# Angelo_Dual_Filter_CTRL_v1_1.net
KiCad netlist of a schematic drawn in EAGLE
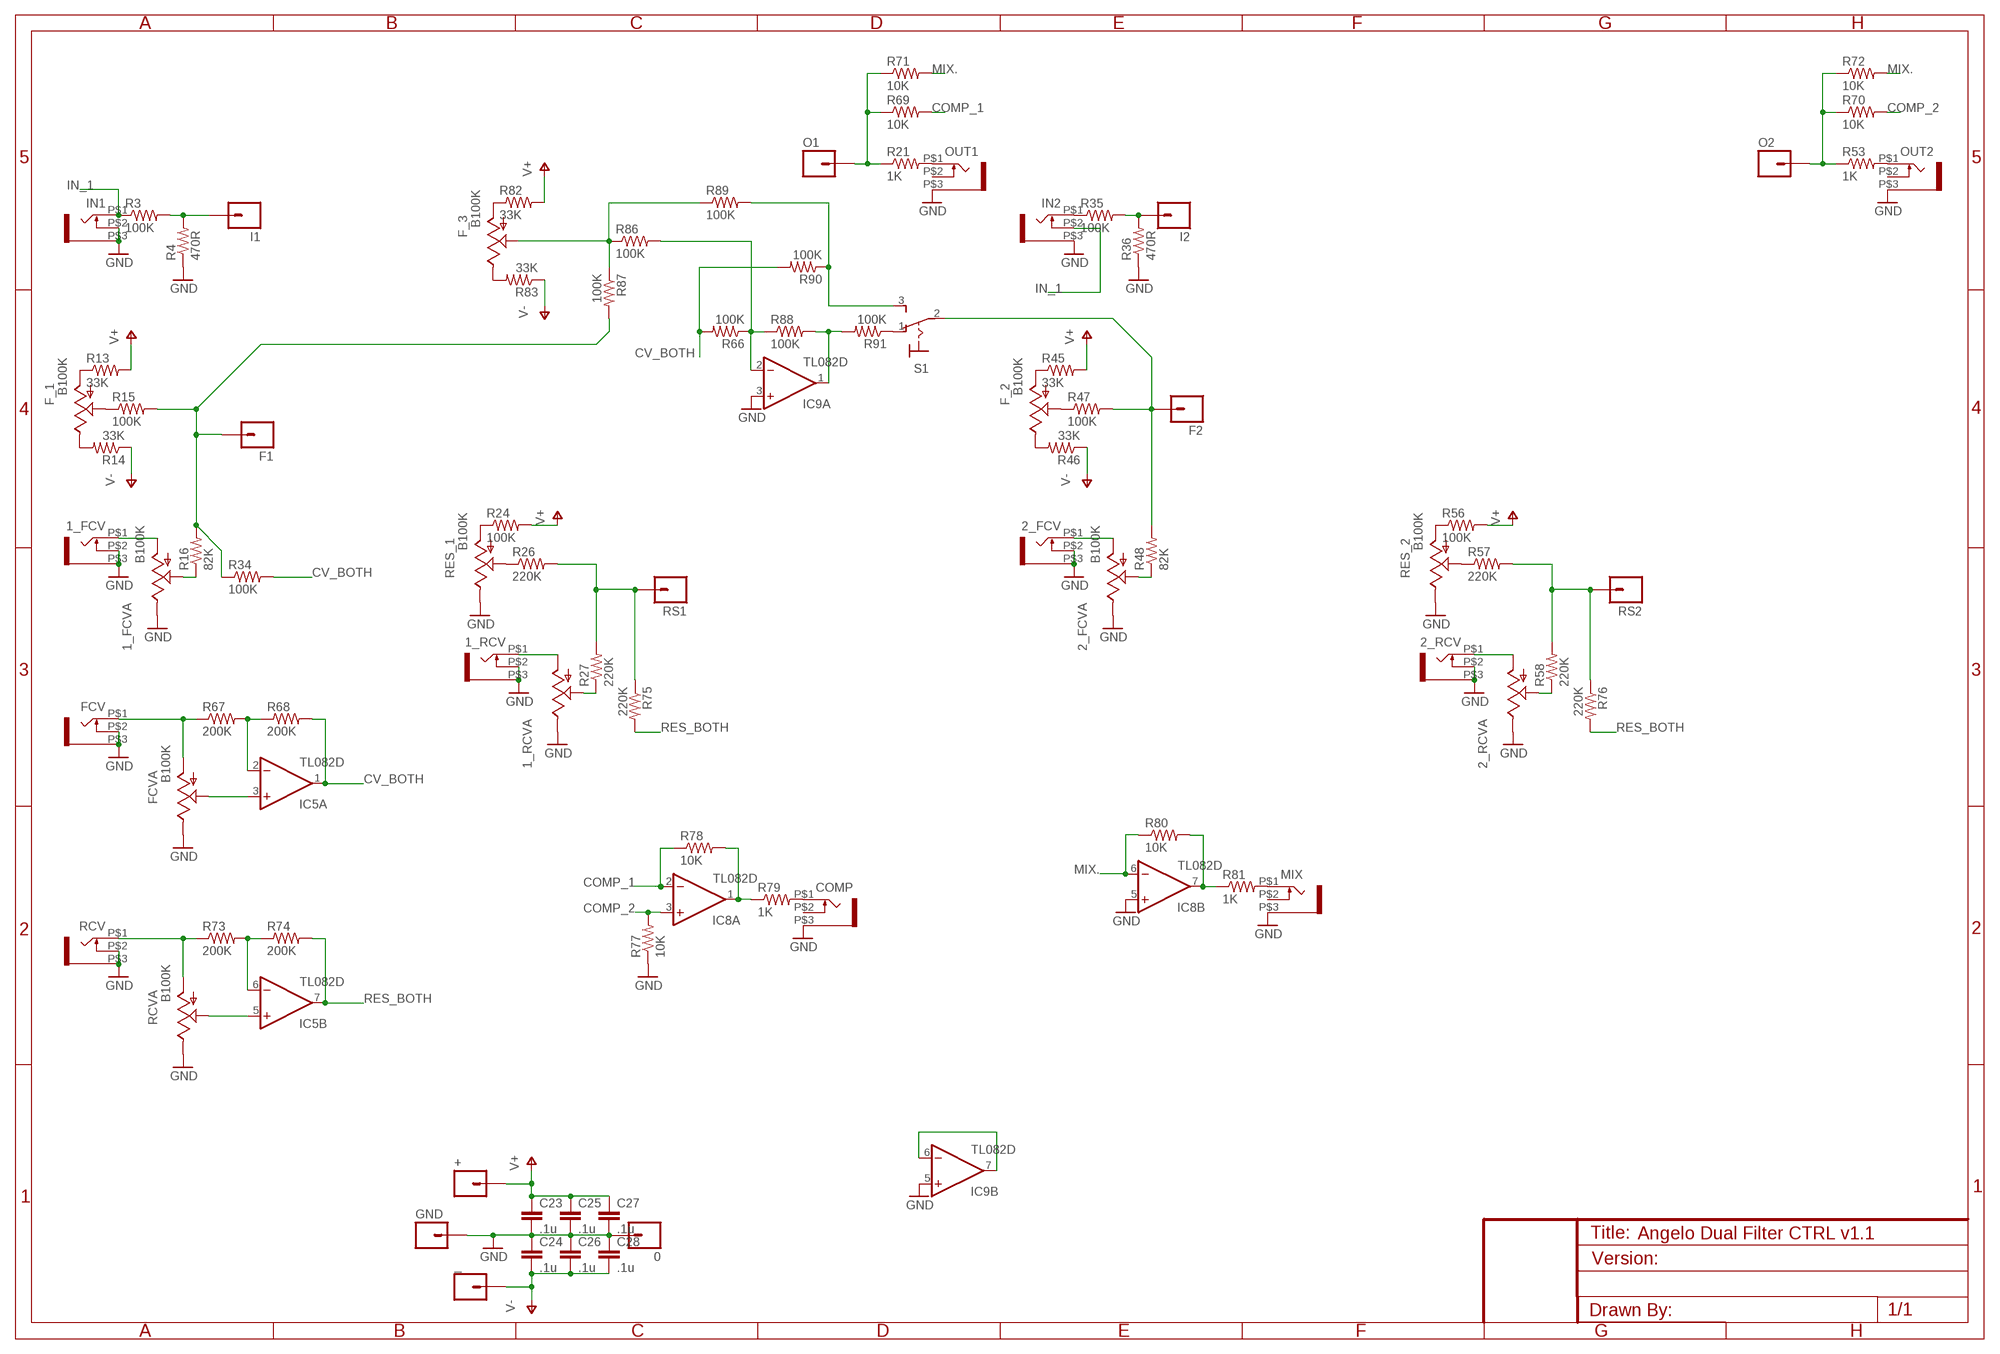
[diagram p0: schematic, sheet 1]

(export (version "E")
  (design (tool "Eeschema 10.0.6"))
  (components
    (comp (ref "+")
      (value "M01PTH")
      (footprint "eagle-import:1X01")
      (libsource (lib "eagle-import") (part "M01PTH"))
    )
    (comp (ref "0")
      (value "M01PTH")
      (footprint "eagle-import:1X01")
      (libsource (lib "eagle-import") (part "M01PTH"))
    )
    (comp (ref "1_FCV")
      (value "WQP-PJ301M-12_JACK")
      (footprint "eagle-import:WQP-PJ301M-12_JACK")
      (libsource (lib "eagle-import") (part "WQP-PJ301M-12_JACK"))
    )
    (comp (ref "1_FCVA")
      (value "B100K")
      (footprint "eagle-import:ALPS_POT")
      (libsource (lib "eagle-import") (part "POT"))
    )
    (comp (ref "1_RCV")
      (value "WQP-PJ301M-12_JACK")
      (footprint "eagle-import:WQP-PJ301M-12_JACK")
      (libsource (lib "eagle-import") (part "WQP-PJ301M-12_JACK"))
    )
    (comp (ref "1_RCVA")
      (value "POT")
      (footprint "eagle-import:ALPS_POT")
      (libsource (lib "eagle-import") (part "POT"))
    )
    (comp (ref "2_FCV")
      (value "WQP-PJ301M-12_JACK")
      (footprint "eagle-import:WQP-PJ301M-12_JACK")
      (libsource (lib "eagle-import") (part "WQP-PJ301M-12_JACK"))
    )
    (comp (ref "2_FCVA")
      (value "B100K")
      (footprint "eagle-import:ALPS_POT")
      (libsource (lib "eagle-import") (part "POT"))
    )
    (comp (ref "2_RCV")
      (value "WQP-PJ301M-12_JACK")
      (footprint "eagle-import:WQP-PJ301M-12_JACK")
      (libsource (lib "eagle-import") (part "WQP-PJ301M-12_JACK"))
    )
    (comp (ref "2_RCVA")
      (value "POT")
      (footprint "eagle-import:ALPS_POT")
      (libsource (lib "eagle-import") (part "POT"))
    )
    (comp (ref "C23")
      (value ".1u")
      (footprint "eagle-import:0805")
      (libsource (lib "eagle-import") (part "CAP0805"))
    )
    (comp (ref "C24")
      (value ".1u")
      (footprint "eagle-import:0805")
      (libsource (lib "eagle-import") (part "CAP0805"))
    )
    (comp (ref "C25")
      (value ".1u")
      (footprint "eagle-import:0805")
      (libsource (lib "eagle-import") (part "CAP0805"))
    )
    (comp (ref "C26")
      (value ".1u")
      (footprint "eagle-import:0805")
      (libsource (lib "eagle-import") (part "CAP0805"))
    )
    (comp (ref "C27")
      (value ".1u")
      (footprint "eagle-import:0805")
      (libsource (lib "eagle-import") (part "CAP0805"))
    )
    (comp (ref "C28")
      (value ".1u")
      (footprint "eagle-import:0805")
      (libsource (lib "eagle-import") (part "CAP0805"))
    )
    (comp (ref "COMP")
      (value "WQP-PJ301M-12_JACK")
      (footprint "eagle-import:WQP-PJ301M-12_JACK")
      (libsource (lib "eagle-import") (part "WQP-PJ301M-12_JACK"))
    )
    (comp (ref "F1")
      (value "M01PTH")
      (footprint "eagle-import:1X01")
      (libsource (lib "eagle-import") (part "M01PTH"))
    )
    (comp (ref "F2")
      (value "M01PTH")
      (footprint "eagle-import:1X01")
      (libsource (lib "eagle-import") (part "M01PTH"))
    )
    (comp (ref "FCV")
      (value "WQP-PJ301M-12_JACK")
      (footprint "eagle-import:WQP-PJ301M-12_JACK")
      (libsource (lib "eagle-import") (part "WQP-PJ301M-12_JACK"))
    )
    (comp (ref "FCVA")
      (value "B100K")
      (footprint "eagle-import:ALPS_POT")
      (libsource (lib "eagle-import") (part "POT"))
    )
    (comp (ref "F_1")
      (value "B100K")
      (footprint "eagle-import:ALPS_POT")
      (libsource (lib "eagle-import") (part "POT"))
    )
    (comp (ref "F_2")
      (value "B100K")
      (footprint "eagle-import:ALPS_POT")
      (libsource (lib "eagle-import") (part "POT"))
    )
    (comp (ref "F_3")
      (value "B100K")
      (footprint "eagle-import:ALPS_POT")
      (libsource (lib "eagle-import") (part "POT"))
    )
    (comp (ref "GND")
      (value "M01PTH")
      (footprint "eagle-import:1X01")
      (libsource (lib "eagle-import") (part "M01PTH"))
    )
    (comp (ref "I1")
      (value "M01PTH")
      (footprint "eagle-import:1X01")
      (libsource (lib "eagle-import") (part "M01PTH"))
    )
    (comp (ref "I2")
      (value "M01PTH")
      (footprint "eagle-import:1X01")
      (libsource (lib "eagle-import") (part "M01PTH"))
    )
    (comp (ref "IC5")
      (value "TL082D")
      (footprint "eagle-import:SO08")
      (libsource (lib "eagle-import") (part "TL082D"))
    )
    (comp (ref "IC8")
      (value "TL082D")
      (footprint "eagle-import:SO08")
      (libsource (lib "eagle-import") (part "TL082D"))
    )
    (comp (ref "IC9")
      (value "TL082D")
      (footprint "eagle-import:SO08")
      (libsource (lib "eagle-import") (part "TL082D"))
    )
    (comp (ref "IN1")
      (value "WQP-PJ301M-12_JACK")
      (footprint "eagle-import:WQP-PJ301M-12_JACK")
      (libsource (lib "eagle-import") (part "WQP-PJ301M-12_JACK"))
    )
    (comp (ref "IN2")
      (value "WQP-PJ301M-12_JACK")
      (footprint "eagle-import:WQP-PJ301M-12_JACK")
      (libsource (lib "eagle-import") (part "WQP-PJ301M-12_JACK"))
    )
    (comp (ref "MIX")
      (value "WQP-PJ301M-12_JACK")
      (footprint "eagle-import:WQP-PJ301M-12_JACK")
      (libsource (lib "eagle-import") (part "WQP-PJ301M-12_JACK"))
    )
    (comp (ref "O1")
      (value "M01PTH")
      (footprint "eagle-import:1X01")
      (libsource (lib "eagle-import") (part "M01PTH"))
    )
    (comp (ref "O2")
      (value "M01PTH")
      (footprint "eagle-import:1X01")
      (libsource (lib "eagle-import") (part "M01PTH"))
    )
    (comp (ref "OUT1")
      (value "WQP-PJ301M-12_JACK")
      (footprint "eagle-import:WQP-PJ301M-12_JACK")
      (libsource (lib "eagle-import") (part "WQP-PJ301M-12_JACK"))
    )
    (comp (ref "OUT2")
      (value "WQP-PJ301M-12_JACK")
      (footprint "eagle-import:WQP-PJ301M-12_JACK")
      (libsource (lib "eagle-import") (part "WQP-PJ301M-12_JACK"))
    )
    (comp (ref "R3")
      (value "100K")
      (footprint "eagle-import:0805")
      (libsource (lib "eagle-import") (part "RESISTOR0805-RES"))
    )
    (comp (ref "R4")
      (value "470R")
      (footprint "eagle-import:0805")
      (libsource (lib "eagle-import") (part "RESISTOR0805-RES"))
    )
    (comp (ref "R13")
      (value "33K")
      (footprint "eagle-import:0805")
      (libsource (lib "eagle-import") (part "RESISTOR0805-RES"))
    )
    (comp (ref "R14")
      (value "33K")
      (footprint "eagle-import:0805")
      (libsource (lib "eagle-import") (part "RESISTOR0805-RES"))
    )
    (comp (ref "R15")
      (value "100K")
      (footprint "eagle-import:0805")
      (libsource (lib "eagle-import") (part "RESISTOR0805-RES"))
    )
    (comp (ref "R16")
      (value "82K")
      (footprint "eagle-import:0805")
      (libsource (lib "eagle-import") (part "RESISTOR0805-RES"))
    )
    (comp (ref "R21")
      (value "1K")
      (footprint "eagle-import:0805")
      (libsource (lib "eagle-import") (part "RESISTOR0805-RES"))
    )
    (comp (ref "R24")
      (value "100K")
      (footprint "eagle-import:0805")
      (libsource (lib "eagle-import") (part "RESISTOR0805-RES"))
    )
    (comp (ref "R26")
      (value "220K")
      (footprint "eagle-import:0805")
      (libsource (lib "eagle-import") (part "RESISTOR0805-RES"))
    )
    (comp (ref "R27")
      (value "220K")
      (footprint "eagle-import:0805")
      (libsource (lib "eagle-import") (part "RESISTOR0805-RES"))
    )
    (comp (ref "R34")
      (value "100K")
      (footprint "eagle-import:0805")
      (libsource (lib "eagle-import") (part "RESISTOR0805-RES"))
    )
    (comp (ref "R35")
      (value "100K")
      (footprint "eagle-import:0805")
      (libsource (lib "eagle-import") (part "RESISTOR0805-RES"))
    )
    (comp (ref "R36")
      (value "470R")
      (footprint "eagle-import:0805")
      (libsource (lib "eagle-import") (part "RESISTOR0805-RES"))
    )
    (comp (ref "R45")
      (value "33K")
      (footprint "eagle-import:0805")
      (libsource (lib "eagle-import") (part "RESISTOR0805-RES"))
    )
    (comp (ref "R46")
      (value "33K")
      (footprint "eagle-import:0805")
      (libsource (lib "eagle-import") (part "RESISTOR0805-RES"))
    )
    (comp (ref "R47")
      (value "100K")
      (footprint "eagle-import:0805")
      (libsource (lib "eagle-import") (part "RESISTOR0805-RES"))
    )
    (comp (ref "R48")
      (value "82K")
      (footprint "eagle-import:0805")
      (libsource (lib "eagle-import") (part "RESISTOR0805-RES"))
    )
    (comp (ref "R53")
      (value "1K")
      (footprint "eagle-import:0805")
      (libsource (lib "eagle-import") (part "RESISTOR0805-RES"))
    )
    (comp (ref "R56")
      (value "100K")
      (footprint "eagle-import:0805")
      (libsource (lib "eagle-import") (part "RESISTOR0805-RES"))
    )
    (comp (ref "R57")
      (value "220K")
      (footprint "eagle-import:0805")
      (libsource (lib "eagle-import") (part "RESISTOR0805-RES"))
    )
    (comp (ref "R58")
      (value "220K")
      (footprint "eagle-import:0805")
      (libsource (lib "eagle-import") (part "RESISTOR0805-RES"))
    )
    (comp (ref "R66")
      (value "100K")
      (footprint "eagle-import:0805")
      (libsource (lib "eagle-import") (part "RESISTOR0805-RES"))
    )
    (comp (ref "R67")
      (value "200K")
      (footprint "eagle-import:0805")
      (libsource (lib "eagle-import") (part "RESISTOR0805-RES"))
    )
    (comp (ref "R68")
      (value "200K")
      (footprint "eagle-import:0805")
      (libsource (lib "eagle-import") (part "RESISTOR0805-RES"))
    )
    (comp (ref "R69")
      (value "10K")
      (footprint "eagle-import:0805")
      (libsource (lib "eagle-import") (part "RESISTOR0805-RES"))
    )
    (comp (ref "R70")
      (value "10K")
      (footprint "eagle-import:0805")
      (libsource (lib "eagle-import") (part "RESISTOR0805-RES"))
    )
    (comp (ref "R71")
      (value "10K")
      (footprint "eagle-import:0805")
      (libsource (lib "eagle-import") (part "RESISTOR0805-RES"))
    )
    (comp (ref "R72")
      (value "10K")
      (footprint "eagle-import:0805")
      (libsource (lib "eagle-import") (part "RESISTOR0805-RES"))
    )
    (comp (ref "R73")
      (value "200K")
      (footprint "eagle-import:0805")
      (libsource (lib "eagle-import") (part "RESISTOR0805-RES"))
    )
    (comp (ref "R74")
      (value "200K")
      (footprint "eagle-import:0805")
      (libsource (lib "eagle-import") (part "RESISTOR0805-RES"))
    )
    (comp (ref "R75")
      (value "220K")
      (footprint "eagle-import:0805")
      (libsource (lib "eagle-import") (part "RESISTOR0805-RES"))
    )
    (comp (ref "R76")
      (value "220K")
      (footprint "eagle-import:0805")
      (libsource (lib "eagle-import") (part "RESISTOR0805-RES"))
    )
    (comp (ref "R77")
      (value "10K")
      (footprint "eagle-import:0805")
      (libsource (lib "eagle-import") (part "RESISTOR0805-RES"))
    )
    (comp (ref "R78")
      (value "10K")
      (footprint "eagle-import:0805")
      (libsource (lib "eagle-import") (part "RESISTOR0805-RES"))
    )
    (comp (ref "R79")
      (value "1K")
      (footprint "eagle-import:0805")
      (libsource (lib "eagle-import") (part "RESISTOR0805-RES"))
    )
    (comp (ref "R80")
      (value "10K")
      (footprint "eagle-import:0805")
      (libsource (lib "eagle-import") (part "RESISTOR0805-RES"))
    )
    (comp (ref "R81")
      (value "1K")
      (footprint "eagle-import:0805")
      (libsource (lib "eagle-import") (part "RESISTOR0805-RES"))
    )
    (comp (ref "R82")
      (value "33K")
      (footprint "eagle-import:0805")
      (libsource (lib "eagle-import") (part "RESISTOR0805-RES"))
    )
    (comp (ref "R83")
      (value "33K")
      (footprint "eagle-import:0805")
      (libsource (lib "eagle-import") (part "RESISTOR0805-RES"))
    )
    (comp (ref "R86")
      (value "100K")
      (footprint "eagle-import:0805")
      (libsource (lib "eagle-import") (part "RESISTOR0805-RES"))
    )
    (comp (ref "R87")
      (value "100K")
      (footprint "eagle-import:0805")
      (libsource (lib "eagle-import") (part "RESISTOR0805-RES"))
    )
    (comp (ref "R88")
      (value "100K")
      (footprint "eagle-import:0805")
      (libsource (lib "eagle-import") (part "RESISTOR0805-RES"))
    )
    (comp (ref "R89")
      (value "100K")
      (footprint "eagle-import:0805")
      (libsource (lib "eagle-import") (part "RESISTOR0805-RES"))
    )
    (comp (ref "R90")
      (value "100K")
      (footprint "eagle-import:0805")
      (libsource (lib "eagle-import") (part "RESISTOR0805-RES"))
    )
    (comp (ref "R91")
      (value "100K")
      (footprint "eagle-import:0805")
      (libsource (lib "eagle-import") (part "RESISTOR0805-RES"))
    )
    (comp (ref "RCV")
      (value "WQP-PJ301M-12_JACK")
      (footprint "eagle-import:WQP-PJ301M-12_JACK")
      (libsource (lib "eagle-import") (part "WQP-PJ301M-12_JACK"))
    )
    (comp (ref "RCVA")
      (value "B100K")
      (footprint "eagle-import:ALPS_POT")
      (libsource (lib "eagle-import") (part "POT"))
    )
    (comp (ref "RES_1")
      (value "B100K")
      (footprint "eagle-import:ALPS_POT")
      (libsource (lib "eagle-import") (part "POT"))
    )
    (comp (ref "RES_2")
      (value "B100K")
      (footprint "eagle-import:ALPS_POT")
      (libsource (lib "eagle-import") (part "POT"))
    )
    (comp (ref "RS1")
      (value "M01PTH")
      (footprint "eagle-import:1X01")
      (libsource (lib "eagle-import") (part "M01PTH"))
    )
    (comp (ref "RS2")
      (value "M01PTH")
      (footprint "eagle-import:1X01")
      (libsource (lib "eagle-import") (part "M01PTH"))
    )
    (comp (ref "S1")
      (value "M9040P")
      (footprint "eagle-import:M9040P")
      (libsource (lib "eagle-import") (part "M9040P"))
    )
    (comp (ref "_")
      (value "M01PTH")
      (footprint "eagle-import:1X01")
      (libsource (lib "eagle-import") (part "M01PTH"))
    )
  )
  (nets
    (net (code "1") (name "/COMP_1") (class "Default")
      (node (ref "IC8") (pin "2") (pinfunction "-IN_2") (pintype "input"))
      (node (ref "R69") (pin "2") (pinfunction "2_2") (pintype "passive"))
      (node (ref "R78") (pin "1") (pinfunction "1_1") (pintype "passive"))
    )
    (net (code "2") (name "/COMP_2") (class "Default")
      (node (ref "IC8") (pin "3") (pinfunction "+IN_3") (pintype "input"))
      (node (ref "R70") (pin "2") (pinfunction "2_2") (pintype "passive"))
      (node (ref "R77") (pin "2") (pinfunction "2_2") (pintype "passive"))
    )
    (net (code "3") (name "/CV_BOTH") (class "Default")
      (node (ref "IC5") (pin "1") (pinfunction "OUT_1") (pintype "output"))
      (node (ref "R34") (pin "2") (pinfunction "2_2") (pintype "passive"))
      (node (ref "R66") (pin "2") (pinfunction "2_2") (pintype "passive"))
      (node (ref "R68") (pin "2") (pinfunction "2_2") (pintype "passive"))
      (node (ref "R90") (pin "2") (pinfunction "2_2") (pintype "passive"))
    )
    (net (code "4") (name "/IN_1") (class "Default")
      (node (ref "IN1") (pin "P$1") (pinfunction "2_P$1") (pintype "passive"))
      (node (ref "IN2") (pin "P$2") (pinfunction "3_P$2") (pintype "passive"))
      (node (ref "R3") (pin "1") (pinfunction "1_1") (pintype "passive"))
    )
    (net (code "5") (name "/MIX.") (class "Default")
      (node (ref "IC8") (pin "6") (pinfunction "-IN_6") (pintype "input"))
      (node (ref "R71") (pin "2") (pinfunction "2_2") (pintype "passive"))
      (node (ref "R72") (pin "2") (pinfunction "2_2") (pintype "passive"))
      (node (ref "R80") (pin "1") (pinfunction "1_1") (pintype "passive"))
    )
    (net (code "6") (name "/RES_BOTH") (class "Default")
      (node (ref "IC5") (pin "7") (pinfunction "OUT_7") (pintype "output"))
      (node (ref "R74") (pin "2") (pinfunction "2_2") (pintype "passive"))
      (node (ref "R75") (pin "2") (pinfunction "2_2") (pintype "passive"))
      (node (ref "R76") (pin "2") (pinfunction "2_2") (pintype "passive"))
    )
    (net (code "7") (name "GND") (class "Default")
      (node (ref "0") (pin "1") (pinfunction "1_1") (pintype "passive"))
      (node (ref "1_FCV") (pin "P$2") (pinfunction "3_P$2") (pintype "passive"))
      (node (ref "1_FCV") (pin "P$3") (pinfunction "1_P$3") (pintype "passive"))
      (node (ref "1_FCVA") (pin "P$1") (pinfunction "E_P$1") (pintype "passive"))
      (node (ref "1_RCV") (pin "P$2") (pinfunction "3_P$2") (pintype "passive"))
      (node (ref "1_RCV") (pin "P$3") (pinfunction "1_P$3") (pintype "passive"))
      (node (ref "1_RCVA") (pin "P$1") (pinfunction "E_P$1") (pintype "passive"))
      (node (ref "2_FCV") (pin "P$2") (pinfunction "3_P$2") (pintype "passive"))
      (node (ref "2_FCV") (pin "P$3") (pinfunction "1_P$3") (pintype "passive"))
      (node (ref "2_FCVA") (pin "P$1") (pinfunction "E_P$1") (pintype "passive"))
      (node (ref "2_RCV") (pin "P$2") (pinfunction "3_P$2") (pintype "passive"))
      (node (ref "2_RCV") (pin "P$3") (pinfunction "1_P$3") (pintype "passive"))
      (node (ref "2_RCVA") (pin "P$1") (pinfunction "E_P$1") (pintype "passive"))
      (node (ref "C23") (pin "2") (pinfunction "2_2") (pintype "passive"))
      (node (ref "C24") (pin "1") (pinfunction "1_1") (pintype "passive"))
      (node (ref "C25") (pin "2") (pinfunction "2_2") (pintype "passive"))
      (node (ref "C26") (pin "1") (pinfunction "1_1") (pintype "passive"))
      (node (ref "C27") (pin "2") (pinfunction "2_2") (pintype "passive"))
      (node (ref "C28") (pin "1") (pinfunction "1_1") (pintype "passive"))
      (node (ref "COMP") (pin "P$3") (pinfunction "1_P$3") (pintype "passive"))
      (node (ref "FCV") (pin "P$2") (pinfunction "3_P$2") (pintype "passive"))
      (node (ref "FCV") (pin "P$3") (pinfunction "1_P$3") (pintype "passive"))
      (node (ref "FCVA") (pin "P$1") (pinfunction "E_P$1") (pintype "passive"))
      (node (ref "GND") (pin "1") (pinfunction "1_1") (pintype "passive"))
      (node (ref "IC8") (pin "5") (pinfunction "+IN_5") (pintype "input"))
      (node (ref "IC9") (pin "3") (pinfunction "+IN_3") (pintype "input"))
      (node (ref "IC9") (pin "5") (pinfunction "+IN_5") (pintype "input"))
      (node (ref "IN1") (pin "P$2") (pinfunction "3_P$2") (pintype "passive"))
      (node (ref "IN1") (pin "P$3") (pinfunction "1_P$3") (pintype "passive"))
      (node (ref "IN2") (pin "P$3") (pinfunction "1_P$3") (pintype "passive"))
      (node (ref "MIX") (pin "P$3") (pinfunction "1_P$3") (pintype "passive"))
      (node (ref "OUT1") (pin "P$3") (pinfunction "1_P$3") (pintype "passive"))
      (node (ref "OUT2") (pin "P$3") (pinfunction "1_P$3") (pintype "passive"))
      (node (ref "R36") (pin "1") (pinfunction "1_1") (pintype "passive"))
      (node (ref "R4") (pin "1") (pinfunction "1_1") (pintype "passive"))
      (node (ref "R77") (pin "1") (pinfunction "1_1") (pintype "passive"))
      (node (ref "RCV") (pin "P$2") (pinfunction "3_P$2") (pintype "passive"))
      (node (ref "RCV") (pin "P$3") (pinfunction "1_P$3") (pintype "passive"))
      (node (ref "RCVA") (pin "P$1") (pinfunction "E_P$1") (pintype "passive"))
      (node (ref "RES_1") (pin "P$1") (pinfunction "E_P$1") (pintype "passive"))
      (node (ref "RES_2") (pin "P$1") (pinfunction "E_P$1") (pintype "passive"))
    )
    (net (code "8") (name "Net-(1_FCV-2)") (class "Default")
      (node (ref "1_FCV") (pin "P$1") (pinfunction "2_P$1") (pintype "passive"))
      (node (ref "1_FCVA") (pin "P$3") (pinfunction "A_P$3") (pintype "passive"))
    )
    (net (code "9") (name "Net-(1_FCVA-S)") (class "Default")
      (node (ref "1_FCVA") (pin "P$2") (pinfunction "S_P$2") (pintype "passive"))
      (node (ref "R16") (pin "1") (pinfunction "1_1") (pintype "passive"))
    )
    (net (code "10") (name "Net-(1_RCV-2)") (class "Default")
      (node (ref "1_RCV") (pin "P$1") (pinfunction "2_P$1") (pintype "passive"))
      (node (ref "1_RCVA") (pin "P$3") (pinfunction "A_P$3") (pintype "passive"))
    )
    (net (code "11") (name "Net-(1_RCVA-S)") (class "Default")
      (node (ref "1_RCVA") (pin "P$2") (pinfunction "S_P$2") (pintype "passive"))
      (node (ref "R27") (pin "1") (pinfunction "1_1") (pintype "passive"))
    )
    (net (code "12") (name "Net-(2_FCV-2)") (class "Default")
      (node (ref "2_FCV") (pin "P$1") (pinfunction "2_P$1") (pintype "passive"))
      (node (ref "2_FCVA") (pin "P$3") (pinfunction "A_P$3") (pintype "passive"))
    )
    (net (code "13") (name "Net-(2_FCVA-S)") (class "Default")
      (node (ref "2_FCVA") (pin "P$2") (pinfunction "S_P$2") (pintype "passive"))
      (node (ref "R48") (pin "1") (pinfunction "1_1") (pintype "passive"))
    )
    (net (code "14") (name "Net-(2_RCV-2)") (class "Default")
      (node (ref "2_RCV") (pin "P$1") (pinfunction "2_P$1") (pintype "passive"))
      (node (ref "2_RCVA") (pin "P$3") (pinfunction "A_P$3") (pintype "passive"))
    )
    (net (code "15") (name "Net-(2_RCVA-S)") (class "Default")
      (node (ref "2_RCVA") (pin "P$2") (pinfunction "S_P$2") (pintype "passive"))
      (node (ref "R58") (pin "1") (pinfunction "1_1") (pintype "passive"))
    )
    (net (code "16") (name "Net-(COMP-2)") (class "Default")
      (node (ref "COMP") (pin "P$1") (pinfunction "2_P$1") (pintype "passive"))
      (node (ref "R79") (pin "2") (pinfunction "2_2") (pintype "passive"))
    )
    (net (code "17") (name "Net-(F1-Pad1)") (class "Default")
      (node (ref "F1") (pin "1") (pinfunction "1_1") (pintype "passive"))
      (node (ref "R15") (pin "2") (pinfunction "2_2") (pintype "passive"))
      (node (ref "R16") (pin "2") (pinfunction "2_2") (pintype "passive"))
      (node (ref "R34") (pin "1") (pinfunction "1_1") (pintype "passive"))
      (node (ref "R87") (pin "2") (pinfunction "2_2") (pintype "passive"))
    )
    (net (code "18") (name "Net-(FCV-2)") (class "Default")
      (node (ref "FCV") (pin "P$1") (pinfunction "2_P$1") (pintype "passive"))
      (node (ref "FCVA") (pin "P$3") (pinfunction "A_P$3") (pintype "passive"))
      (node (ref "R67") (pin "1") (pinfunction "1_1") (pintype "passive"))
    )
    (net (code "19") (name "Net-(FCVA-S)") (class "Default")
      (node (ref "FCVA") (pin "P$2") (pinfunction "S_P$2") (pintype "passive"))
      (node (ref "IC5") (pin "3") (pinfunction "+IN_3") (pintype "input"))
    )
    (net (code "20") (name "Net-(F_1-A)") (class "Default")
      (node (ref "F_1") (pin "P$3") (pinfunction "A_P$3") (pintype "passive"))
      (node (ref "R13") (pin "1") (pinfunction "1_1") (pintype "passive"))
    )
    (net (code "21") (name "Net-(F_1-E)") (class "Default")
      (node (ref "F_1") (pin "P$1") (pinfunction "E_P$1") (pintype "passive"))
      (node (ref "R14") (pin "2") (pinfunction "2_2") (pintype "passive"))
    )
    (net (code "22") (name "Net-(F_1-S)") (class "Default")
      (node (ref "F_1") (pin "P$2") (pinfunction "S_P$2") (pintype "passive"))
      (node (ref "R15") (pin "1") (pinfunction "1_1") (pintype "passive"))
    )
    (net (code "23") (name "Net-(F_2-A)") (class "Default")
      (node (ref "F_2") (pin "P$3") (pinfunction "A_P$3") (pintype "passive"))
      (node (ref "R45") (pin "1") (pinfunction "1_1") (pintype "passive"))
    )
    (net (code "24") (name "Net-(F_2-E)") (class "Default")
      (node (ref "F_2") (pin "P$1") (pinfunction "E_P$1") (pintype "passive"))
      (node (ref "R46") (pin "2") (pinfunction "2_2") (pintype "passive"))
    )
    (net (code "25") (name "Net-(F_2-S)") (class "Default")
      (node (ref "F_2") (pin "P$2") (pinfunction "S_P$2") (pintype "passive"))
      (node (ref "R47") (pin "1") (pinfunction "1_1") (pintype "passive"))
    )
    (net (code "26") (name "Net-(F_3-A)") (class "Default")
      (node (ref "F_3") (pin "P$3") (pinfunction "A_P$3") (pintype "passive"))
      (node (ref "R82") (pin "1") (pinfunction "1_1") (pintype "passive"))
    )
    (net (code "27") (name "Net-(F_3-E)") (class "Default")
      (node (ref "F_3") (pin "P$1") (pinfunction "E_P$1") (pintype "passive"))
      (node (ref "R83") (pin "2") (pinfunction "2_2") (pintype "passive"))
    )
    (net (code "28") (name "Net-(F_3-S)") (class "Default")
      (node (ref "F_3") (pin "P$2") (pinfunction "S_P$2") (pintype "passive"))
      (node (ref "R86") (pin "1") (pinfunction "1_1") (pintype "passive"))
      (node (ref "R87") (pin "1") (pinfunction "1_1") (pintype "passive"))
      (node (ref "R89") (pin "1") (pinfunction "1_1") (pintype "passive"))
    )
    (net (code "29") (name "Net-(I1-Pad1)") (class "Default")
      (node (ref "I1") (pin "1") (pinfunction "1_1") (pintype "passive"))
      (node (ref "R3") (pin "2") (pinfunction "2_2") (pintype "passive"))
      (node (ref "R4") (pin "2") (pinfunction "2_2") (pintype "passive"))
    )
    (net (code "30") (name "Net-(I2-Pad1)") (class "Default")
      (node (ref "I2") (pin "1") (pinfunction "1_1") (pintype "passive"))
      (node (ref "R35") (pin "2") (pinfunction "2_2") (pintype "passive"))
      (node (ref "R36") (pin "2") (pinfunction "2_2") (pintype "passive"))
    )
    (net (code "31") (name "Net-(IC5A--IN)") (class "Default")
      (node (ref "IC5") (pin "2") (pinfunction "-IN_2") (pintype "input"))
      (node (ref "R67") (pin "2") (pinfunction "2_2") (pintype "passive"))
      (node (ref "R68") (pin "1") (pinfunction "1_1") (pintype "passive"))
    )
    (net (code "32") (name "Net-(IC5B-+IN)") (class "Default")
      (node (ref "IC5") (pin "5") (pinfunction "+IN_5") (pintype "input"))
      (node (ref "RCVA") (pin "P$2") (pinfunction "S_P$2") (pintype "passive"))
    )
    (net (code "33") (name "Net-(IC5B--IN)") (class "Default")
      (node (ref "IC5") (pin "6") (pinfunction "-IN_6") (pintype "input"))
      (node (ref "R73") (pin "2") (pinfunction "2_2") (pintype "passive"))
      (node (ref "R74") (pin "1") (pinfunction "1_1") (pintype "passive"))
    )
    (net (code "34") (name "Net-(IC8A-OUT)") (class "Default")
      (node (ref "IC8") (pin "1") (pinfunction "OUT_1") (pintype "output"))
      (node (ref "R78") (pin "2") (pinfunction "2_2") (pintype "passive"))
      (node (ref "R79") (pin "1") (pinfunction "1_1") (pintype "passive"))
    )
    (net (code "35") (name "Net-(IC8B-OUT)") (class "Default")
      (node (ref "IC8") (pin "7") (pinfunction "OUT_7") (pintype "output"))
      (node (ref "R80") (pin "2") (pinfunction "2_2") (pintype "passive"))
      (node (ref "R81") (pin "1") (pinfunction "1_1") (pintype "passive"))
    )
    (net (code "36") (name "Net-(IC9A--IN)") (class "Default")
      (node (ref "IC9") (pin "2") (pinfunction "-IN_2") (pintype "input"))
      (node (ref "R66") (pin "1") (pinfunction "1_1") (pintype "passive"))
      (node (ref "R86") (pin "2") (pinfunction "2_2") (pintype "passive"))
      (node (ref "R88") (pin "1") (pinfunction "1_1") (pintype "passive"))
    )
    (net (code "37") (name "Net-(IC9A-OUT)") (class "Default")
      (node (ref "IC9") (pin "1") (pinfunction "OUT_1") (pintype "output"))
      (node (ref "R88") (pin "2") (pinfunction "2_2") (pintype "passive"))
      (node (ref "R91") (pin "2") (pinfunction "2_2") (pintype "passive"))
    )
    (net (code "38") (name "Net-(IC9B--IN)") (class "Default")
      (node (ref "IC9") (pin "6") (pinfunction "-IN_6") (pintype "input"))
      (node (ref "IC9") (pin "7") (pinfunction "OUT_7") (pintype "output"))
    )
    (net (code "39") (name "Net-(IN2-2)") (class "Default")
      (node (ref "IN2") (pin "P$1") (pinfunction "2_P$1") (pintype "passive"))
      (node (ref "R35") (pin "1") (pinfunction "1_1") (pintype "passive"))
    )
    (net (code "40") (name "Net-(MIX-2)") (class "Default")
      (node (ref "MIX") (pin "P$1") (pinfunction "2_P$1") (pintype "passive"))
      (node (ref "R81") (pin "2") (pinfunction "2_2") (pintype "passive"))
    )
    (net (code "41") (name "Net-(O1-Pad1)") (class "Default")
      (node (ref "O1") (pin "1") (pinfunction "1_1") (pintype "passive"))
      (node (ref "R21") (pin "1") (pinfunction "1_1") (pintype "passive"))
      (node (ref "R69") (pin "1") (pinfunction "1_1") (pintype "passive"))
      (node (ref "R71") (pin "1") (pinfunction "1_1") (pintype "passive"))
    )
    (net (code "42") (name "Net-(O2-Pad1)") (class "Default")
      (node (ref "O2") (pin "1") (pinfunction "1_1") (pintype "passive"))
      (node (ref "R53") (pin "1") (pinfunction "1_1") (pintype "passive"))
      (node (ref "R70") (pin "1") (pinfunction "1_1") (pintype "passive"))
      (node (ref "R72") (pin "1") (pinfunction "1_1") (pintype "passive"))
    )
    (net (code "43") (name "Net-(OUT1-2)") (class "Default")
      (node (ref "OUT1") (pin "P$1") (pinfunction "2_P$1") (pintype "passive"))
      (node (ref "R21") (pin "2") (pinfunction "2_2") (pintype "passive"))
    )
    (net (code "44") (name "Net-(OUT2-2)") (class "Default")
      (node (ref "OUT2") (pin "P$1") (pinfunction "2_P$1") (pintype "passive"))
      (node (ref "R53") (pin "2") (pinfunction "2_2") (pintype "passive"))
    )
    (net (code "45") (name "Net-(R26-Pad2)") (class "Default")
      (node (ref "R26") (pin "2") (pinfunction "2_2") (pintype "passive"))
      (node (ref "R27") (pin "2") (pinfunction "2_2") (pintype "passive"))
      (node (ref "R75") (pin "1") (pinfunction "1_1") (pintype "passive"))
      (node (ref "RS1") (pin "1") (pinfunction "1_1") (pintype "passive"))
    )
    (net (code "46") (name "Net-(R57-Pad2)") (class "Default")
      (node (ref "R57") (pin "2") (pinfunction "2_2") (pintype "passive"))
      (node (ref "R58") (pin "2") (pinfunction "2_2") (pintype "passive"))
      (node (ref "R76") (pin "1") (pinfunction "1_1") (pintype "passive"))
      (node (ref "RS2") (pin "1") (pinfunction "1_1") (pintype "passive"))
    )
    (net (code "47") (name "Net-(RCV-2)") (class "Default")
      (node (ref "R73") (pin "1") (pinfunction "1_1") (pintype "passive"))
      (node (ref "RCV") (pin "P$1") (pinfunction "2_P$1") (pintype "passive"))
      (node (ref "RCVA") (pin "P$3") (pinfunction "A_P$3") (pintype "passive"))
    )
    (net (code "48") (name "Net-(RES_1-A)") (class "Default")
      (node (ref "R24") (pin "1") (pinfunction "1_1") (pintype "passive"))
      (node (ref "RES_1") (pin "P$3") (pinfunction "A_P$3") (pintype "passive"))
    )
    (net (code "49") (name "Net-(RES_1-S)") (class "Default")
      (node (ref "R26") (pin "1") (pinfunction "1_1") (pintype "passive"))
      (node (ref "RES_1") (pin "P$2") (pinfunction "S_P$2") (pintype "passive"))
    )
    (net (code "50") (name "Net-(RES_2-A)") (class "Default")
      (node (ref "R56") (pin "1") (pinfunction "1_1") (pintype "passive"))
      (node (ref "RES_2") (pin "P$3") (pinfunction "A_P$3") (pintype "passive"))
    )
    (net (code "51") (name "Net-(RES_2-S)") (class "Default")
      (node (ref "R57") (pin "1") (pinfunction "1_1") (pintype "passive"))
      (node (ref "RES_2") (pin "P$2") (pinfunction "S_P$2") (pintype "passive"))
    )
    (net (code "52") (name "Net-(S1-O)") (class "Default")
      (node (ref "R91") (pin "1") (pinfunction "1_1") (pintype "passive"))
      (node (ref "S1") (pin "1") (pinfunction "O_1") (pintype "passive"))
    )
    (net (code "53") (name "Net-(S1-P)") (class "Default")
      (node (ref "F2") (pin "1") (pinfunction "1_1") (pintype "passive"))
      (node (ref "R47") (pin "2") (pinfunction "2_2") (pintype "passive"))
      (node (ref "R48") (pin "2") (pinfunction "2_2") (pintype "passive"))
      (node (ref "S1") (pin "2") (pinfunction "P_2") (pintype "passive"))
    )
    (net (code "54") (name "Net-(S1-S)") (class "Default")
      (node (ref "R89") (pin "2") (pinfunction "2_2") (pintype "passive"))
      (node (ref "R90") (pin "1") (pinfunction "1_1") (pintype "passive"))
      (node (ref "S1") (pin "3") (pinfunction "S_3") (pintype "passive"))
    )
    (net (code "55") (name "V+") (class "Default")
      (node (ref "+") (pin "1") (pinfunction "1_1") (pintype "passive"))
      (node (ref "C23") (pin "1") (pinfunction "1_1") (pintype "passive"))
      (node (ref "C25") (pin "1") (pinfunction "1_1") (pintype "passive"))
      (node (ref "C27") (pin "1") (pinfunction "1_1") (pintype "passive"))
      (node (ref "R13") (pin "2") (pinfunction "2_2") (pintype "passive"))
      (node (ref "R24") (pin "2") (pinfunction "2_2") (pintype "passive"))
      (node (ref "R45") (pin "2") (pinfunction "2_2") (pintype "passive"))
      (node (ref "R56") (pin "2") (pinfunction "2_2") (pintype "passive"))
      (node (ref "R82") (pin "2") (pinfunction "2_2") (pintype "passive"))
    )
    (net (code "56") (name "V-") (class "Default")
      (node (ref "C24") (pin "2") (pinfunction "2_2") (pintype "passive"))
      (node (ref "C26") (pin "2") (pinfunction "2_2") (pintype "passive"))
      (node (ref "C28") (pin "2") (pinfunction "2_2") (pintype "passive"))
      (node (ref "R14") (pin "1") (pinfunction "1_1") (pintype "passive"))
      (node (ref "R46") (pin "1") (pinfunction "1_1") (pintype "passive"))
      (node (ref "R83") (pin "1") (pinfunction "1_1") (pintype "passive"))
      (node (ref "_") (pin "1") (pinfunction "1_1") (pintype "passive"))
    )
    (net (code "57") (name "unconnected-(COMP-3-PadP$2)") (class "Default")
      (node (ref "COMP") (pin "P$2") (pinfunction "3_P$2") (pintype "passive"))
    )
    (net (code "58") (name "unconnected-(MIX-3-PadP$2)") (class "Default")
      (node (ref "MIX") (pin "P$2") (pinfunction "3_P$2") (pintype "passive"))
    )
    (net (code "59") (name "unconnected-(OUT1-3-PadP$2)") (class "Default")
      (node (ref "OUT1") (pin "P$2") (pinfunction "3_P$2") (pintype "passive"))
    )
    (net (code "60") (name "unconnected-(OUT2-3-PadP$2)") (class "Default")
      (node (ref "OUT2") (pin "P$2") (pinfunction "3_P$2") (pintype "passive"))
    )
  )
)
